# schematic_gps.net
KiCad netlist of a schematic drawn in EAGLE
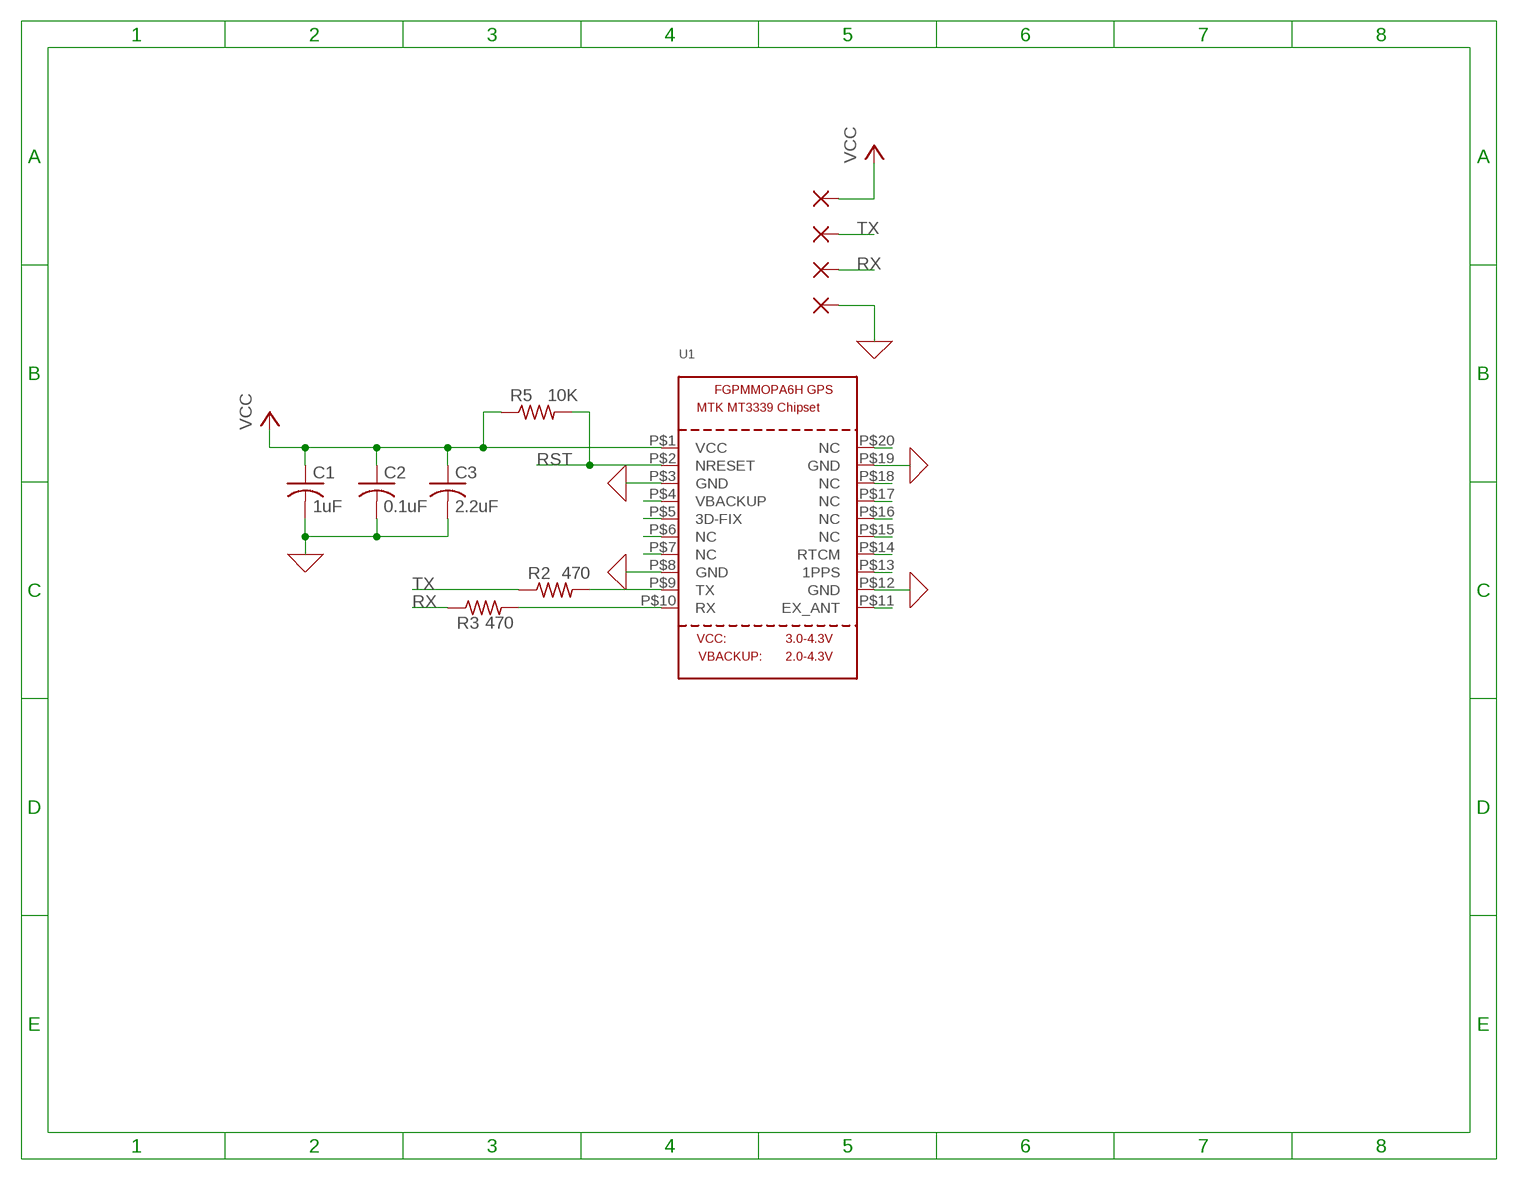
[diagram p0: schematic, sheet 1]

(export (version "E")
  (design (tool "Eeschema 10.0.6"))
  (components
    (comp (ref "C1")
      (value "1uF")
      (footprint "eagle-import:C0805")
      (libsource (lib "eagle-import") (part "C-USC0805"))
    )
    (comp (ref "C2")
      (value "0.1uF")
      (footprint "eagle-import:C0805")
      (libsource (lib "eagle-import") (part "C-USC0805"))
    )
    (comp (ref "C3")
      (value "2.2uF")
      (footprint "eagle-import:C0805")
      (libsource (lib "eagle-import") (part "C-USC0805"))
    )
    (comp (ref "GND")
      (value "WIREPADSMD1,27-254")
      (footprint "eagle-import:SMD1,27-2,54")
      (libsource (lib "eagle-import") (part "WIREPADSMD1,27-254"))
    )
    (comp (ref "R2")
      (value "470")
      (footprint "eagle-import:R0805")
      (libsource (lib "eagle-import") (part "R-US_R0805"))
    )
    (comp (ref "R3")
      (value "470")
      (footprint "eagle-import:R0805")
      (libsource (lib "eagle-import") (part "R-US_R0805"))
    )
    (comp (ref "R5")
      (value "10K")
      (footprint "eagle-import:R0805")
      (libsource (lib "eagle-import") (part "R-US_R0805"))
    )
    (comp (ref "RX")
      (value "WIREPADSMD1,27-254")
      (footprint "eagle-import:SMD1,27-2,54")
      (libsource (lib "eagle-import") (part "WIREPADSMD1,27-254"))
    )
    (comp (ref "TX")
      (value "WIREPADSMD1,27-254")
      (footprint "eagle-import:SMD1,27-2,54")
      (libsource (lib "eagle-import") (part "WIREPADSMD1,27-254"))
    )
    (comp (ref "U1")
      (value "GPS_FGPMMOPA6H")
      (footprint "eagle-import:FGPMMOPA6H")
      (fields (field (name "SPICEPREFIX") "X"))
      (libsource (lib "eagle-import") (part "GPS_FGPMMOPA6H"))
    )
    (comp (ref "VCC")
      (value "WIREPADSMD1,27-254")
      (footprint "eagle-import:SMD1,27-2,54")
      (libsource (lib "eagle-import") (part "WIREPADSMD1,27-254"))
    )
  )
  (nets
    (net (code "1") (name "/RST") (class "Default")
      (node (ref "R5") (pin "2") (pinfunction "2_2") (pintype "passive"))
      (node (ref "U1") (pin "P$2") (pinfunction "NRESET_P$2") (pintype "bidirectional"))
    )
    (net (code "2") (name "/RX") (class "Default")
      (node (ref "R3") (pin "1") (pinfunction "1_1") (pintype "passive"))
      (node (ref "RX") (pin "1") (pinfunction "P_1") (pintype "passive"))
    )
    (net (code "3") (name "/TX") (class "Default")
      (node (ref "R2") (pin "1") (pinfunction "1_1") (pintype "passive"))
      (node (ref "TX") (pin "1") (pinfunction "P_1") (pintype "passive"))
    )
    (net (code "4") (name "GND") (class "Default")
      (node (ref "C1") (pin "2") (pinfunction "2_2") (pintype "passive"))
      (node (ref "C2") (pin "2") (pinfunction "2_2") (pintype "passive"))
      (node (ref "C3") (pin "2") (pinfunction "2_2") (pintype "passive"))
      (node (ref "GND") (pin "1") (pinfunction "P_1") (pintype "passive"))
      (node (ref "U1") (pin "P$12") (pinfunction "GND_P$12") (pintype "bidirectional"))
      (node (ref "U1") (pin "P$19") (pinfunction "GND_P$19") (pintype "bidirectional"))
      (node (ref "U1") (pin "P$3") (pinfunction "GND_P$3") (pintype "bidirectional"))
      (node (ref "U1") (pin "P$8") (pinfunction "GND_P$8") (pintype "bidirectional"))
    )
    (net (code "5") (name "Net-(U1-RX)") (class "Default")
      (node (ref "R3") (pin "2") (pinfunction "2_2") (pintype "passive"))
      (node (ref "U1") (pin "P$10") (pinfunction "RX_P$10") (pintype "bidirectional"))
    )
    (net (code "6") (name "Net-(U1-TX)") (class "Default")
      (node (ref "R2") (pin "2") (pinfunction "2_2") (pintype "passive"))
      (node (ref "U1") (pin "P$9") (pinfunction "TX_P$9") (pintype "bidirectional"))
    )
    (net (code "7") (name "VCC") (class "Default")
      (node (ref "C1") (pin "1") (pinfunction "1_1") (pintype "passive"))
      (node (ref "C2") (pin "1") (pinfunction "1_1") (pintype "passive"))
      (node (ref "C3") (pin "1") (pinfunction "1_1") (pintype "passive"))
      (node (ref "R5") (pin "1") (pinfunction "1_1") (pintype "passive"))
      (node (ref "U1") (pin "P$1") (pinfunction "VCC_P$1") (pintype "bidirectional"))
      (node (ref "VCC") (pin "1") (pinfunction "P_1") (pintype "passive"))
    )
    (net (code "8") (name "unconnected-(U1-1PPS-PadP$13)") (class "Default")
      (node (ref "U1") (pin "P$13") (pinfunction "1PPS_P$13") (pintype "bidirectional"))
    )
    (net (code "9") (name "unconnected-(U1-3D-FIX-PadP$5)") (class "Default")
      (node (ref "U1") (pin "P$5") (pinfunction "3D-FIX_P$5") (pintype "bidirectional"))
    )
    (net (code "10") (name "unconnected-(U1-EX_ANT-PadP$11)") (class "Default")
      (node (ref "U1") (pin "P$11") (pinfunction "EX_ANT_P$11") (pintype "bidirectional"))
    )
    (net (code "11") (name "unconnected-(U1-NC-PadP$6)") (class "Default")
      (node (ref "U1") (pin "P$6") (pinfunction "NC_P$6") (pintype "bidirectional"))
    )
    (net (code "12") (name "unconnected-(U1-NC-PadP$7)") (class "Default")
      (node (ref "U1") (pin "P$7") (pinfunction "NC_P$7") (pintype "bidirectional"))
    )
    (net (code "13") (name "unconnected-(U1-NC-PadP$15)") (class "Default")
      (node (ref "U1") (pin "P$15") (pinfunction "NC_P$15") (pintype "bidirectional"))
    )
    (net (code "14") (name "unconnected-(U1-NC-PadP$16)") (class "Default")
      (node (ref "U1") (pin "P$16") (pinfunction "NC_P$16") (pintype "bidirectional"))
    )
    (net (code "15") (name "unconnected-(U1-NC-PadP$17)") (class "Default")
      (node (ref "U1") (pin "P$17") (pinfunction "NC_P$17") (pintype "bidirectional"))
    )
    (net (code "16") (name "unconnected-(U1-NC-PadP$18)") (class "Default")
      (node (ref "U1") (pin "P$18") (pinfunction "NC_P$18") (pintype "bidirectional"))
    )
    (net (code "17") (name "unconnected-(U1-NC-PadP$20)") (class "Default")
      (node (ref "U1") (pin "P$20") (pinfunction "NC_P$20") (pintype "bidirectional"))
    )
    (net (code "18") (name "unconnected-(U1-RTCM-PadP$14)") (class "Default")
      (node (ref "U1") (pin "P$14") (pinfunction "RTCM_P$14") (pintype "bidirectional"))
    )
    (net (code "19") (name "unconnected-(U1-VBACKUP-PadP$4)") (class "Default")
      (node (ref "U1") (pin "P$4") (pinfunction "VBACKUP_P$4") (pintype "bidirectional"))
    )
  )
)
